# 4_output_Igniter.net
KiCad netlist of a schematic drawn in EAGLE
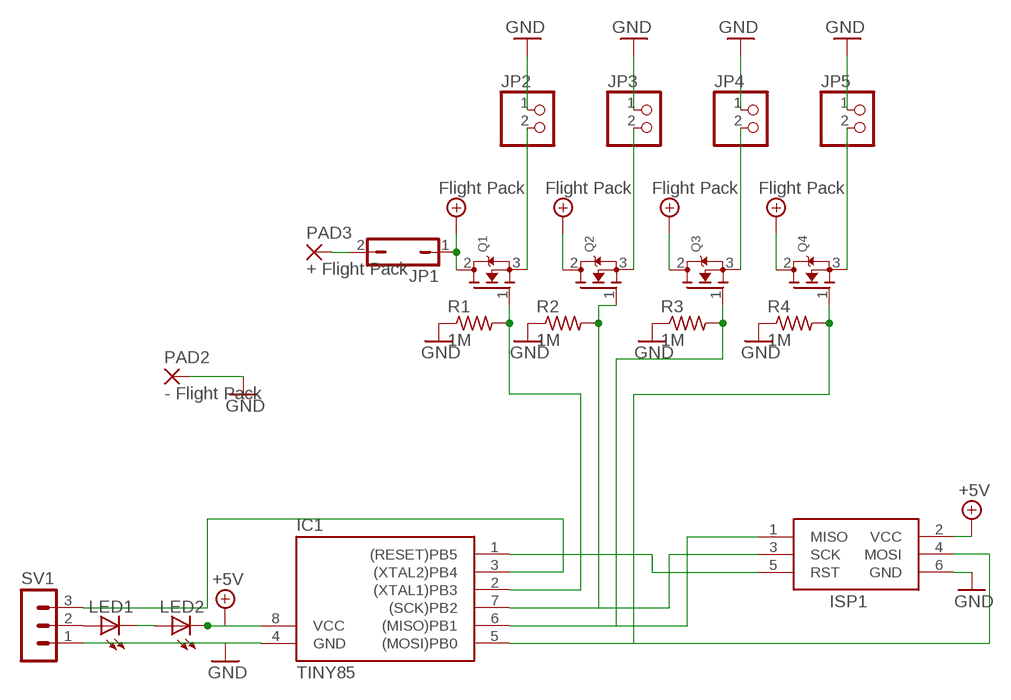
[diagram p0: schematic, sheet 1]

(export (version "E")
  (design (tool "Eeschema 10.0.6"))
  (components
    (comp (ref "IC1")
      (value "TINY85")
      (footprint "eagle-import:DIL08")
      (libsource (lib "eagle-import") (part "TINY12P"))
    )
    (comp (ref "ISP1")
      (value "AVRISP-6")
      (footprint "eagle-import:AVRISP")
      (libsource (lib "eagle-import") (part "AVRISP-6"))
    )
    (comp (ref "JP1")
      (value "JP1Q")
      (footprint "eagle-import:JP1")
      (libsource (lib "eagle-import") (part "JP1Q"))
    )
    (comp (ref "JP2")
      (value "PINHD-1X2")
      (footprint "eagle-import:1X02")
      (libsource (lib "eagle-import") (part "PINHD-1X2"))
    )
    (comp (ref "JP3")
      (value "PINHD-1X2")
      (footprint "eagle-import:1X02")
      (libsource (lib "eagle-import") (part "PINHD-1X2"))
    )
    (comp (ref "JP4")
      (value "PINHD-1X2")
      (footprint "eagle-import:1X02")
      (libsource (lib "eagle-import") (part "PINHD-1X2"))
    )
    (comp (ref "JP5")
      (value "PINHD-1X2")
      (footprint "eagle-import:1X02")
      (libsource (lib "eagle-import") (part "PINHD-1X2"))
    )
    (comp (ref "LED1")
      (value "LED3MM")
      (footprint "eagle-import:LED3MM")
      (libsource (lib "eagle-import") (part "LED3MM"))
    )
    (comp (ref "LED2")
      (value "LED3MM")
      (footprint "eagle-import:LED3MM")
      (libsource (lib "eagle-import") (part "LED3MM"))
    )
    (comp (ref "PAD2")
      (value "- Flight Pack")
      (footprint "eagle-import:2,15_1,0")
      (libsource (lib "eagle-import") (part "2,15/1,0"))
    )
    (comp (ref "PAD3")
      (value "+ Flight Pack")
      (footprint "eagle-import:2,15_1,0")
      (libsource (lib "eagle-import") (part "2,15/1,0"))
    )
    (comp (ref "Q1")
      (value "MOSFET-NGDS_TO220V")
      (footprint "eagle-import:TO220V")
      (libsource (lib "eagle-import") (part "MOSFET-NGDS_TO220V"))
    )
    (comp (ref "Q2")
      (value "MOSFET-NGDS_TO220V")
      (footprint "eagle-import:TO220V")
      (libsource (lib "eagle-import") (part "MOSFET-NGDS_TO220V"))
    )
    (comp (ref "Q3")
      (value "MOSFET-NGDS_TO220V")
      (footprint "eagle-import:TO220V")
      (libsource (lib "eagle-import") (part "MOSFET-NGDS_TO220V"))
    )
    (comp (ref "Q4")
      (value "MOSFET-NGDS_TO220V")
      (footprint "eagle-import:TO220V")
      (libsource (lib "eagle-import") (part "MOSFET-NGDS_TO220V"))
    )
    (comp (ref "R1")
      (value "1M")
      (footprint "eagle-import:0204V")
      (libsource (lib "eagle-import") (part "R-US_0204/2V"))
    )
    (comp (ref "R2")
      (value "1M")
      (footprint "eagle-import:0204V")
      (libsource (lib "eagle-import") (part "R-US_0204/2V"))
    )
    (comp (ref "R3")
      (value "1M")
      (footprint "eagle-import:0204V")
      (libsource (lib "eagle-import") (part "R-US_0204/2V"))
    )
    (comp (ref "R4")
      (value "1M")
      (footprint "eagle-import:0204V")
      (libsource (lib "eagle-import") (part "R-US_0204/2V"))
    )
    (comp (ref "SV1")
      (value "MA03-1")
      (footprint "eagle-import:MA03-1")
      (libsource (lib "eagle-import") (part "MA03-1"))
    )
  )
  (nets
    (net (code "1") (name "+5V") (class "Default")
      (node (ref "IC1") (pin "8") (pinfunction "VCC_8") (pintype "power_in"))
      (node (ref "ISP1") (pin "2") (pinfunction "VCC_2") (pintype "power_in"))
      (node (ref "LED2") (pin "K") (pinfunction "C_K") (pintype "passive"))
    )
    (net (code "2") (name "Flight Pack") (class "Default")
      (node (ref "JP1") (pin "1") (pinfunction "1_1") (pintype "passive"))
      (node (ref "Q1") (pin "2") (pinfunction "D_2") (pintype "bidirectional"))
      (node (ref "Q2") (pin "2") (pinfunction "D_2") (pintype "bidirectional"))
      (node (ref "Q3") (pin "2") (pinfunction "D_2") (pintype "bidirectional"))
      (node (ref "Q4") (pin "2") (pinfunction "D_2") (pintype "bidirectional"))
    )
    (net (code "3") (name "GND") (class "Default")
      (node (ref "IC1") (pin "4") (pinfunction "GND_4") (pintype "power_in"))
      (node (ref "ISP1") (pin "6") (pinfunction "GND_6") (pintype "power_in"))
      (node (ref "JP2") (pin "1") (pinfunction "1_1") (pintype "passive"))
      (node (ref "JP3") (pin "1") (pinfunction "1_1") (pintype "passive"))
      (node (ref "JP4") (pin "1") (pinfunction "1_1") (pintype "passive"))
      (node (ref "JP5") (pin "1") (pinfunction "1_1") (pintype "passive"))
      (node (ref "PAD2") (pin "1") (pinfunction "P_1") (pintype "passive"))
      (node (ref "R1") (pin "1") (pinfunction "1_1") (pintype "passive"))
      (node (ref "R2") (pin "1") (pinfunction "1_1") (pintype "passive"))
      (node (ref "R3") (pin "1") (pinfunction "1_1") (pintype "passive"))
      (node (ref "R4") (pin "1") (pinfunction "1_1") (pintype "passive"))
      (node (ref "SV1") (pin "1") (pinfunction "1_1") (pintype "passive"))
    )
    (net (code "4") (name "Net-(IC1-(MISO)PB1)") (class "Default")
      (node (ref "IC1") (pin "6") (pinfunction "(MISO)PB1_6") (pintype "bidirectional"))
      (node (ref "ISP1") (pin "1") (pinfunction "MISO_1") (pintype "input"))
      (node (ref "Q3") (pin "1") (pinfunction "G_1") (pintype "bidirectional"))
      (node (ref "R3") (pin "2") (pinfunction "2_2") (pintype "passive"))
    )
    (net (code "5") (name "Net-(IC1-(MOSI)PB0)") (class "Default")
      (node (ref "IC1") (pin "5") (pinfunction "(MOSI)PB0_5") (pintype "bidirectional"))
      (node (ref "ISP1") (pin "4") (pinfunction "MOSI_4") (pintype "output"))
      (node (ref "Q4") (pin "1") (pinfunction "G_1") (pintype "bidirectional"))
      (node (ref "R4") (pin "2") (pinfunction "2_2") (pintype "passive"))
    )
    (net (code "6") (name "Net-(IC1-(RESET)PB5)") (class "Default")
      (node (ref "IC1") (pin "1") (pinfunction "(RESET)PB5_1") (pintype "bidirectional"))
      (node (ref "ISP1") (pin "5") (pinfunction "RST_5") (pintype "output"))
    )
    (net (code "7") (name "Net-(IC1-(SCK)PB2)") (class "Default")
      (node (ref "IC1") (pin "7") (pinfunction "(SCK)PB2_7") (pintype "bidirectional"))
      (node (ref "ISP1") (pin "3") (pinfunction "SCK_3") (pintype "output"))
      (node (ref "Q2") (pin "1") (pinfunction "G_1") (pintype "bidirectional"))
      (node (ref "R2") (pin "2") (pinfunction "2_2") (pintype "passive"))
    )
    (net (code "8") (name "Net-(IC1-(XTAL1)PB3)") (class "Default")
      (node (ref "IC1") (pin "2") (pinfunction "(XTAL1)PB3_2") (pintype "bidirectional"))
      (node (ref "Q1") (pin "1") (pinfunction "G_1") (pintype "bidirectional"))
      (node (ref "R1") (pin "2") (pinfunction "2_2") (pintype "passive"))
    )
    (net (code "9") (name "Net-(IC1-(XTAL2)PB4)") (class "Default")
      (node (ref "IC1") (pin "3") (pinfunction "(XTAL2)PB4_3") (pintype "bidirectional"))
      (node (ref "SV1") (pin "3") (pinfunction "3_3") (pintype "passive"))
    )
    (net (code "10") (name "Net-(LED1-C)") (class "Default")
      (node (ref "LED1") (pin "K") (pinfunction "C_K") (pintype "passive"))
      (node (ref "LED2") (pin "A") (pinfunction "A_A") (pintype "passive"))
    )
    (net (code "11") (name "Net-(LED1-PadA)") (class "Default")
      (node (ref "LED1") (pin "A") (pinfunction "A_A") (pintype "passive"))
      (node (ref "SV1") (pin "2") (pinfunction "2_2") (pintype "passive"))
    )
    (net (code "12") (name "Net-(PAD3-P)") (class "Default")
      (node (ref "JP1") (pin "2") (pinfunction "2_2") (pintype "passive"))
      (node (ref "PAD3") (pin "1") (pinfunction "P_1") (pintype "passive"))
    )
    (net (code "13") (name "Net-(Q1-S)") (class "Default")
      (node (ref "JP2") (pin "2") (pinfunction "2_2") (pintype "passive"))
      (node (ref "Q1") (pin "3") (pinfunction "S_3") (pintype "bidirectional"))
    )
    (net (code "14") (name "Net-(Q2-S)") (class "Default")
      (node (ref "JP3") (pin "2") (pinfunction "2_2") (pintype "passive"))
      (node (ref "Q2") (pin "3") (pinfunction "S_3") (pintype "bidirectional"))
    )
    (net (code "15") (name "Net-(Q3-S)") (class "Default")
      (node (ref "JP4") (pin "2") (pinfunction "2_2") (pintype "passive"))
      (node (ref "Q3") (pin "3") (pinfunction "S_3") (pintype "bidirectional"))
    )
    (net (code "16") (name "Net-(Q4-S)") (class "Default")
      (node (ref "JP5") (pin "2") (pinfunction "2_2") (pintype "passive"))
      (node (ref "Q4") (pin "3") (pinfunction "S_3") (pintype "bidirectional"))
    )
  )
)
